# dimmer_microcontrolado.net
KiCad netlist of a schematic drawn in EAGLE
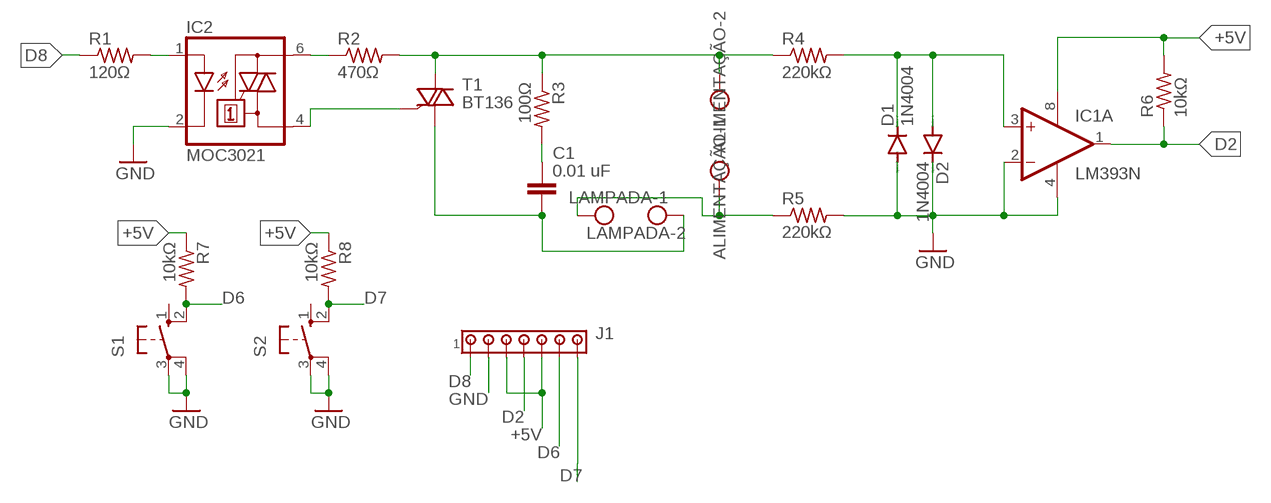
[diagram p0: schematic, sheet 1]

(export (version "E")
  (design (tool "Eeschema 10.0.6"))
  (components
    (comp (ref "ALIMENTAÇÃO")
      (value "AK300/2")
      (footprint "eagle-import:AK300_2")
      (libsource (lib "eagle-import") (part "AK300/2"))
    )
    (comp (ref "C1")
      (value "0.01 uF")
      (footprint "eagle-import:C075-032X103")
      (libsource (lib "eagle-import") (part "C-EU075-032X103"))
    )
    (comp (ref "D1")
      (value "1N4004")
      (footprint "eagle-import:DO35-7")
      (libsource (lib "eagle-import") (part "1N4148DO35-7"))
    )
    (comp (ref "D2")
      (value "1N4004")
      (footprint "eagle-import:DO35-7")
      (libsource (lib "eagle-import") (part "1N4148DO35-7"))
    )
    (comp (ref "IC1")
      (value "LM393N")
      (footprint "eagle-import:DIL08")
      (libsource (lib "eagle-import") (part "LM393N"))
    )
    (comp (ref "IC2")
      (value "MOC3021")
      (footprint "eagle-import:DIL06")
      (fields (field (name "MF") "FAIRCHILD SEMICONDUCTOR") (field (name "MPN") "MOC3021-M"))
      (libsource (lib "eagle-import") (part "MOC30M21"))
    )
    (comp (ref "J1")
      (value "MTA07-100")
      (footprint "eagle-import:10X07MTA")
      (libsource (lib "eagle-import") (part "MTA07-100"))
    )
    (comp (ref "LAMPADA")
      (value "AK300/2")
      (footprint "eagle-import:AK300_2")
      (libsource (lib "eagle-import") (part "AK300/2"))
    )
    (comp (ref "R1")
      (value "120Ω")
      (footprint "eagle-import:0207_10")
      (libsource (lib "eagle-import") (part "R-US_0207/10"))
    )
    (comp (ref "R2")
      (value "470Ω")
      (footprint "eagle-import:0207_10")
      (libsource (lib "eagle-import") (part "R-US_0207/10"))
    )
    (comp (ref "R3")
      (value "100Ω")
      (footprint "eagle-import:0207_10")
      (libsource (lib "eagle-import") (part "R-US_0207/10"))
    )
    (comp (ref "R4")
      (value "220kΩ")
      (footprint "eagle-import:0207_10")
      (libsource (lib "eagle-import") (part "R-US_0207/10"))
    )
    (comp (ref "R5")
      (value "220kΩ")
      (footprint "eagle-import:0207_10")
      (libsource (lib "eagle-import") (part "R-US_0207/10"))
    )
    (comp (ref "R6")
      (value "10kΩ")
      (footprint "eagle-import:0207_10")
      (libsource (lib "eagle-import") (part "R-US_0207/10"))
    )
    (comp (ref "R7")
      (value "10kΩ")
      (footprint "eagle-import:0207_10")
      (libsource (lib "eagle-import") (part "R-US_0207/10"))
    )
    (comp (ref "R8")
      (value "10kΩ")
      (footprint "eagle-import:0207_10")
      (libsource (lib "eagle-import") (part "R-US_0207/10"))
    )
    (comp (ref "S1")
      (value "10-XX")
      (footprint "eagle-import:B3F-10XX")
      (fields (field (name "MPN") "B3F-1000"))
      (libsource (lib "eagle-import") (part "10-XX"))
    )
    (comp (ref "S2")
      (value "10-XX")
      (footprint "eagle-import:B3F-10XX")
      (fields (field (name "MPN") "B3F-1000"))
      (libsource (lib "eagle-import") (part "10-XX"))
    )
    (comp (ref "T1")
      (value "BT136")
      (footprint "eagle-import:TO220AB")
      (libsource (lib "eagle-import") (part "BT136"))
    )
  )
  (nets
    (net (code "1") (name "+5V") (class "Default")
      (node (ref "IC1") (pin "8") (pinfunction "V+_8") (pintype "power_in"))
      (node (ref "J1") (pin "3") (pinfunction "3_3") (pintype "passive"))
      (node (ref "J1") (pin "5") (pinfunction "5_5") (pintype "passive"))
      (node (ref "R6") (pin "2") (pinfunction "2_2") (pintype "passive"))
      (node (ref "R7") (pin "1") (pinfunction "1_1") (pintype "passive"))
      (node (ref "R8") (pin "1") (pinfunction "1_1") (pintype "passive"))
    )
    (net (code "2") (name "/D6") (class "Default")
      (node (ref "J1") (pin "6") (pinfunction "6_6") (pintype "passive"))
      (node (ref "R7") (pin "2") (pinfunction "2_2") (pintype "passive"))
      (node (ref "S1") (pin "2") (pinfunction "S1_2") (pintype "passive"))
    )
    (net (code "3") (name "/D7") (class "Default")
      (node (ref "J1") (pin "7") (pinfunction "7_7") (pintype "passive"))
      (node (ref "R8") (pin "2") (pinfunction "2_2") (pintype "passive"))
      (node (ref "S2") (pin "2") (pinfunction "S1_2") (pintype "passive"))
    )
    (net (code "4") (name "D2") (class "Default")
      (node (ref "IC1") (pin "1") (pinfunction "OUT_1") (pintype "output"))
      (node (ref "J1") (pin "4") (pinfunction "4_4") (pintype "passive"))
      (node (ref "R6") (pin "1") (pinfunction "1_1") (pintype "passive"))
    )
    (net (code "5") (name "D8") (class "Default")
      (node (ref "J1") (pin "1") (pinfunction "1_1") (pintype "passive"))
      (node (ref "R1") (pin "1") (pinfunction "1_1") (pintype "passive"))
    )
    (net (code "6") (name "GND") (class "Default")
      (node (ref "D1") (pin "A") (pinfunction "A_A") (pintype "passive"))
      (node (ref "D2") (pin "C") (pinfunction "C_C") (pintype "passive"))
      (node (ref "IC1") (pin "2") (pinfunction "-IN_2") (pintype "input"))
      (node (ref "IC1") (pin "4") (pinfunction "V-_4") (pintype "power_in"))
      (node (ref "IC2") (pin "2") (pinfunction "C_2") (pintype "passive"))
      (node (ref "J1") (pin "2") (pinfunction "2_2") (pintype "passive"))
      (node (ref "R5") (pin "2") (pinfunction "2_2") (pintype "passive"))
      (node (ref "S1") (pin "3") (pinfunction "P_3") (pintype "passive"))
      (node (ref "S1") (pin "4") (pinfunction "P1_4") (pintype "passive"))
      (node (ref "S2") (pin "3") (pinfunction "P_3") (pintype "passive"))
      (node (ref "S2") (pin "4") (pinfunction "P1_4") (pintype "passive"))
    )
    (net (code "7") (name "Net-(ALIMENTAÇÃOA-KL)") (class "Default")
      (node (ref "ALIMENTAÇÃO") (pin "1") (pinfunction "KL_1") (pintype "passive"))
      (node (ref "R2") (pin "2") (pinfunction "2_2") (pintype "passive"))
      (node (ref "R3") (pin "1") (pinfunction "1_1") (pintype "passive"))
      (node (ref "R4") (pin "1") (pinfunction "1_1") (pintype "passive"))
      (node (ref "T1") (pin "2") (pinfunction "A2_2") (pintype "passive"))
    )
    (net (code "8") (name "Net-(ALIMENTAÇÃOB-KL)") (class "Default")
      (node (ref "ALIMENTAÇÃO") (pin "2") (pinfunction "KL_2") (pintype "passive"))
      (node (ref "LAMPADA") (pin "1") (pinfunction "KL_1") (pintype "passive"))
      (node (ref "R5") (pin "1") (pinfunction "1_1") (pintype "passive"))
    )
    (net (code "9") (name "Net-(C1-Pad1)") (class "Default")
      (node (ref "C1") (pin "1") (pinfunction "1_1") (pintype "passive"))
      (node (ref "R3") (pin "2") (pinfunction "2_2") (pintype "passive"))
    )
    (net (code "10") (name "Net-(IC1A-+IN)") (class "Default")
      (node (ref "D1") (pin "C") (pinfunction "C_C") (pintype "passive"))
      (node (ref "D2") (pin "A") (pinfunction "A_A") (pintype "passive"))
      (node (ref "IC1") (pin "3") (pinfunction "+IN_3") (pintype "input"))
      (node (ref "R4") (pin "2") (pinfunction "2_2") (pintype "passive"))
    )
    (net (code "11") (name "Net-(IC2-A)") (class "Default")
      (node (ref "IC2") (pin "1") (pinfunction "A_1") (pintype "passive"))
      (node (ref "R1") (pin "2") (pinfunction "2_2") (pintype "passive"))
    )
    (net (code "12") (name "Net-(IC2-A1)") (class "Default")
      (node (ref "IC2") (pin "4") (pinfunction "A1_4") (pintype "passive"))
      (node (ref "T1") (pin "3") (pinfunction "G_3") (pintype "passive"))
    )
    (net (code "13") (name "Net-(IC2-A2)") (class "Default")
      (node (ref "IC2") (pin "6") (pinfunction "A2_6") (pintype "passive"))
      (node (ref "R2") (pin "1") (pinfunction "1_1") (pintype "passive"))
    )
    (net (code "14") (name "Net-(LAMPADAB-KL)") (class "Default")
      (node (ref "C1") (pin "2") (pinfunction "2_2") (pintype "passive"))
      (node (ref "LAMPADA") (pin "2") (pinfunction "KL_2") (pintype "passive"))
      (node (ref "T1") (pin "1") (pinfunction "A1_1") (pintype "passive"))
    )
    (net (code "15") (name "unconnected-(S1-S-Pad1)") (class "Default")
      (node (ref "S1") (pin "1") (pinfunction "S_1") (pintype "passive"))
    )
    (net (code "16") (name "unconnected-(S2-S-Pad1)") (class "Default")
      (node (ref "S2") (pin "1") (pinfunction "S_1") (pintype "passive"))
    )
  )
)
